# arm.net
KiCad netlist of a schematic drawn in EAGLE
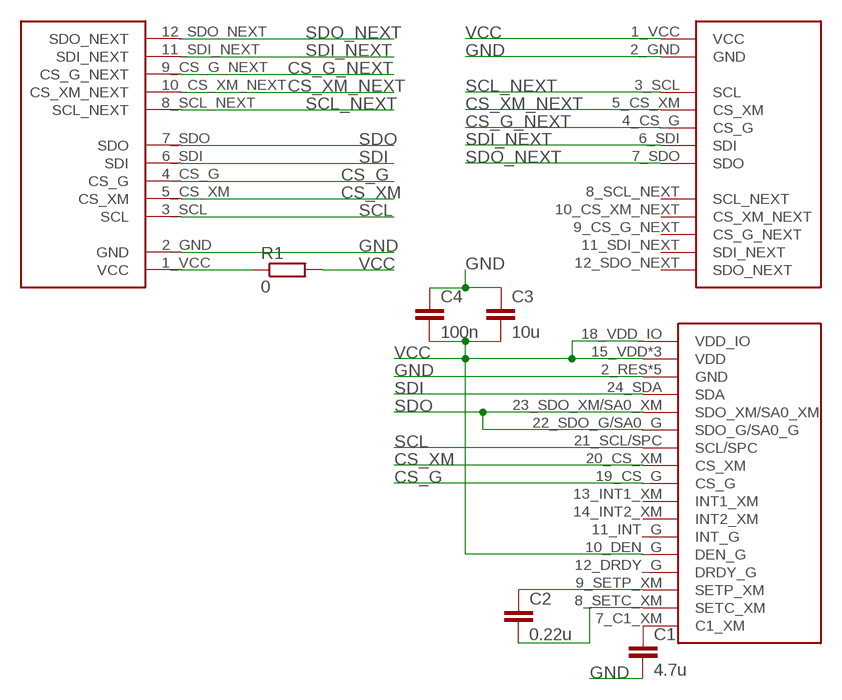
[diagram p0: schematic, sheet 1]

(export (version "E")
  (design (tool "Eeschema 10.0.6"))
  (components
    (comp (ref "C1")
      (value "4.7u")
      (footprint "eagle-import:C0805")
      (libsource (lib "eagle-import") (part "C-EUC0805"))
    )
    (comp (ref "C2")
      (value "0.22u")
      (footprint "eagle-import:C0805")
      (libsource (lib "eagle-import") (part "C-EUC0805"))
    )
    (comp (ref "C3")
      (value "10u")
      (footprint "eagle-import:C0805")
      (libsource (lib "eagle-import") (part "C-EUC0805"))
    )
    (comp (ref "C4")
      (value "100n")
      (footprint "eagle-import:C0603")
      (libsource (lib "eagle-import") (part "resistor_C-EUC0603"))
    )
    (comp (ref "IMU_IN")
      (value "IMU-BUCHSE-IN")
      (footprint "eagle-import:IN")
      (libsource (lib "eagle-import") (part "IMU-BUCHSE-IN"))
    )
    (comp (ref "IMU_OUT")
      (value "IMU-BUCHSE-OUT")
      (footprint "eagle-import:OUT")
      (libsource (lib "eagle-import") (part "IMU-BUCHSE-OUT"))
    )
    (comp (ref "R1")
      (value "0")
      (footprint "eagle-import:R0402")
      (libsource (lib "eagle-import") (part "R-EU_R0402"))
    )
    (comp (ref "U$1")
      (value "LSM9DS0-LGA-24")
      (footprint "eagle-import:LGA-24")
      (libsource (lib "eagle-import") (part "LSM9DS0-LGA-24"))
    )
  )
  (nets
    (net (code "1") (name "/CS_G") (class "Default")
      (node (ref "IMU_IN") (pin "4_CS_G") (pinfunction "CS_G_4_CS_G") (pintype "bidirectional"))
      (node (ref "U$1") (pin "19_CS_G") (pinfunction "CS_G_19_CS_G") (pintype "bidirectional"))
    )
    (net (code "2") (name "/CS_G_NEXT") (class "Default")
      (node (ref "IMU_IN") (pin "9_CS_G_NEXT") (pinfunction "CS_G_NEXT_9_CS_G_NEXT") (pintype "bidirectional"))
      (node (ref "IMU_OUT") (pin "4_CS_G") (pinfunction "CS_G_4_CS_G") (pintype "bidirectional"))
    )
    (net (code "3") (name "/CS_XM") (class "Default")
      (node (ref "IMU_IN") (pin "5_CS_XM") (pinfunction "CS_XM_5_CS_XM") (pintype "bidirectional"))
      (node (ref "U$1") (pin "20_CS_XM") (pinfunction "CS_XM_20_CS_XM") (pintype "bidirectional"))
    )
    (net (code "4") (name "/CS_XM_NEXT") (class "Default")
      (node (ref "IMU_IN") (pin "10_CS_XM_NEXT") (pinfunction "CS_XM_NEXT_10_CS_XM_NEXT") (pintype "bidirectional"))
      (node (ref "IMU_OUT") (pin "5_CS_XM") (pinfunction "CS_XM_5_CS_XM") (pintype "bidirectional"))
    )
    (net (code "5") (name "/GND") (class "Default")
      (node (ref "C1") (pin "2") (pinfunction "2_2") (pintype "passive"))
      (node (ref "C3") (pin "1") (pinfunction "1_1") (pintype "passive"))
      (node (ref "C4") (pin "1") (pinfunction "1_1") (pintype "passive"))
      (node (ref "IMU_IN") (pin "2_GND") (pinfunction "GND_2_GND") (pintype "bidirectional"))
      (node (ref "IMU_OUT") (pin "2_GND") (pinfunction "GND_2_GND") (pintype "bidirectional"))
      (node (ref "U$1") (pin "2_RES") (pinfunction "GND_2_RES") (pintype "bidirectional"))
      (node (ref "U$1") (pin "3_RES") (pinfunction "GND_3_RES") (pintype "bidirectional"))
      (node (ref "U$1") (pin "4_RES") (pinfunction "GND_4_RES") (pintype "bidirectional"))
      (node (ref "U$1") (pin "5_GND") (pinfunction "GND_5_GND") (pintype "bidirectional"))
      (node (ref "U$1") (pin "6_GND") (pinfunction "GND_6_GND") (pintype "bidirectional"))
    )
    (net (code "6") (name "/SCL") (class "Default")
      (node (ref "IMU_IN") (pin "3_SCL") (pinfunction "SCL_3_SCL") (pintype "bidirectional"))
      (node (ref "U$1") (pin "21_SCL/SPC") (pinfunction "SCL/SPC_21_SCL/SPC") (pintype "bidirectional"))
    )
    (net (code "7") (name "/SCL_NEXT") (class "Default")
      (node (ref "IMU_IN") (pin "8_SCL_NEXT") (pinfunction "SCL_NEXT_8_SCL_NEXT") (pintype "bidirectional"))
      (node (ref "IMU_OUT") (pin "3_SCL") (pinfunction "SCL_3_SCL") (pintype "bidirectional"))
    )
    (net (code "8") (name "/SDI") (class "Default")
      (node (ref "IMU_IN") (pin "6_SDI") (pinfunction "SDI_6_SDI") (pintype "bidirectional"))
      (node (ref "U$1") (pin "24_SDA") (pinfunction "SDA_24_SDA") (pintype "bidirectional"))
    )
    (net (code "9") (name "/SDI_NEXT") (class "Default")
      (node (ref "IMU_IN") (pin "11_SDI_NEXT") (pinfunction "SDI_NEXT_11_SDI_NEXT") (pintype "bidirectional"))
      (node (ref "IMU_OUT") (pin "6_SDI") (pinfunction "SDI_6_SDI") (pintype "bidirectional"))
    )
    (net (code "10") (name "/SDO") (class "Default")
      (node (ref "IMU_IN") (pin "7_SDO") (pinfunction "SDO_7_SDO") (pintype "bidirectional"))
      (node (ref "U$1") (pin "22_SDO_G/SA0_G") (pinfunction "SDO_G/SA0_G_22_SDO_G/SA0_G") (pintype "bidirectional"))
      (node (ref "U$1") (pin "23_SDO_XM/SA0_XM") (pinfunction "SDO_XM/SA0_XM_23_SDO_XM/SA0_XM") (pintype "bidirectional"))
    )
    (net (code "11") (name "/SDO_NEXT") (class "Default")
      (node (ref "IMU_IN") (pin "12_SDO_NEXT") (pinfunction "SDO_NEXT_12_SDO_NEXT") (pintype "bidirectional"))
      (node (ref "IMU_OUT") (pin "7_SDO") (pinfunction "SDO_7_SDO") (pintype "bidirectional"))
    )
    (net (code "12") (name "/VCC") (class "Default")
      (node (ref "C3") (pin "2") (pinfunction "2_2") (pintype "passive"))
      (node (ref "C4") (pin "2") (pinfunction "2_2") (pintype "passive"))
      (node (ref "IMU_OUT") (pin "1_VCC") (pinfunction "VCC_1_VCC") (pintype "bidirectional"))
      (node (ref "R1") (pin "2") (pinfunction "2_2") (pintype "passive"))
      (node (ref "U$1") (pin "10_DEN_G") (pinfunction "DEN_G_10_DEN_G") (pintype "bidirectional"))
      (node (ref "U$1") (pin "15_VDD") (pinfunction "VDD_15_VDD") (pintype "bidirectional"))
      (node (ref "U$1") (pin "16_VDD") (pinfunction "VDD_16_VDD") (pintype "bidirectional"))
      (node (ref "U$1") (pin "17_VDD") (pinfunction "VDD_17_VDD") (pintype "bidirectional"))
      (node (ref "U$1") (pin "18_VDD_IO") (pinfunction "VDD_IO_18_VDD_IO") (pintype "bidirectional"))
    )
    (net (code "13") (name "Net-(IMU_IN-VCC)") (class "Default")
      (node (ref "IMU_IN") (pin "1_VCC") (pinfunction "VCC_1_VCC") (pintype "bidirectional"))
      (node (ref "R1") (pin "1") (pinfunction "1_1") (pintype "passive"))
    )
    (net (code "14") (name "Net-(U$1-C1_XM)") (class "Default")
      (node (ref "C1") (pin "1") (pinfunction "1_1") (pintype "passive"))
      (node (ref "U$1") (pin "7_C1_XM") (pinfunction "C1_XM_7_C1_XM") (pintype "bidirectional"))
    )
    (net (code "15") (name "Net-(U$1-SETC_XM)") (class "Default")
      (node (ref "C2") (pin "2") (pinfunction "2_2") (pintype "passive"))
      (node (ref "U$1") (pin "8_SETC_XM") (pinfunction "SETC_XM_8_SETC_XM") (pintype "bidirectional"))
    )
    (net (code "16") (name "Net-(U$1-SETP_XM)") (class "Default")
      (node (ref "C2") (pin "1") (pinfunction "1_1") (pintype "passive"))
      (node (ref "U$1") (pin "9_SETP_XM") (pinfunction "SETP_XM_9_SETP_XM") (pintype "bidirectional"))
    )
    (net (code "17") (name "unconnected-(IMU_OUT-CS_G_NEXT-Pad9_CS_G_NEXT)") (class "Default")
      (node (ref "IMU_OUT") (pin "9_CS_G_NEXT") (pinfunction "CS_G_NEXT_9_CS_G_NEXT") (pintype "bidirectional"))
    )
    (net (code "18") (name "unconnected-(IMU_OUT-CS_XM_NEXT-Pad10_CS_XM_NEXT)") (class "Default")
      (node (ref "IMU_OUT") (pin "10_CS_XM_NEXT") (pinfunction "CS_XM_NEXT_10_CS_XM_NEXT") (pintype "bidirectional"))
    )
    (net (code "19") (name "unconnected-(IMU_OUT-SCL_NEXT-Pad8_SCL_NEXT)") (class "Default")
      (node (ref "IMU_OUT") (pin "8_SCL_NEXT") (pinfunction "SCL_NEXT_8_SCL_NEXT") (pintype "bidirectional"))
    )
    (net (code "20") (name "unconnected-(IMU_OUT-SDI_NEXT-Pad11_SDI_NEXT)") (class "Default")
      (node (ref "IMU_OUT") (pin "11_SDI_NEXT") (pinfunction "SDI_NEXT_11_SDI_NEXT") (pintype "bidirectional"))
    )
    (net (code "21") (name "unconnected-(IMU_OUT-SDO_NEXT-Pad12_SDO_NEXT)") (class "Default")
      (node (ref "IMU_OUT") (pin "12_SDO_NEXT") (pinfunction "SDO_NEXT_12_SDO_NEXT") (pintype "bidirectional"))
    )
    (net (code "22") (name "unconnected-(U$1-DRDY_G-Pad12_DRDY_G)") (class "Default")
      (node (ref "U$1") (pin "12_DRDY_G") (pinfunction "DRDY_G_12_DRDY_G") (pintype "bidirectional"))
    )
    (net (code "23") (name "unconnected-(U$1-INT1_XM-Pad13_INT1_XM)") (class "Default")
      (node (ref "U$1") (pin "13_INT1_XM") (pinfunction "INT1_XM_13_INT1_XM") (pintype "bidirectional"))
    )
    (net (code "24") (name "unconnected-(U$1-INT2_XM-Pad14_INT2_XM)") (class "Default")
      (node (ref "U$1") (pin "14_INT2_XM") (pinfunction "INT2_XM_14_INT2_XM") (pintype "bidirectional"))
    )
    (net (code "25") (name "unconnected-(U$1-INT_G-Pad11_INT_G)") (class "Default")
      (node (ref "U$1") (pin "11_INT_G") (pinfunction "INT_G_11_INT_G") (pintype "bidirectional"))
    )
  )
)
